# TIA_sep_amp_13_March.net
KiCad netlist of a schematic drawn in EAGLE
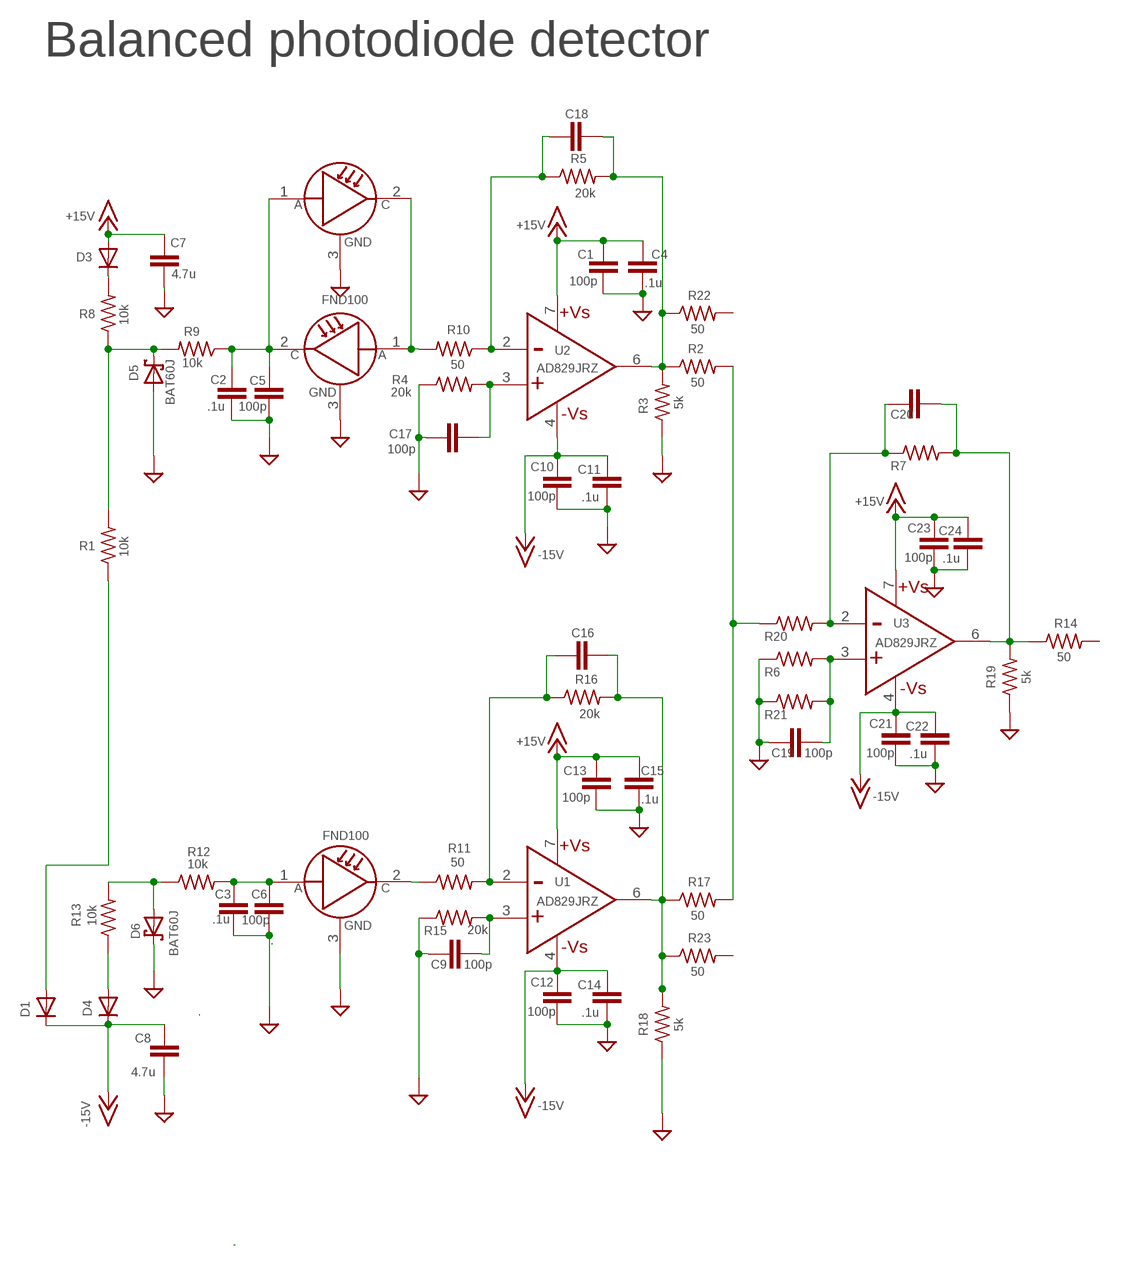
[diagram p0: schematic, sheet 1]

(export (version "E")
  (design (tool "Eeschema 10.0.6"))
  (components
    (comp (ref "C1")
      (value "100p")
      (footprint "eagle-import:C0603")
      (libsource (lib "eagle-import") (part "C-EUC0603"))
    )
    (comp (ref "C2")
      (value ".1u")
      (footprint "eagle-import:C0603")
      (libsource (lib "eagle-import") (part "C-EUC0603"))
    )
    (comp (ref "C3")
      (value ".1u")
      (footprint "eagle-import:C0603")
      (libsource (lib "eagle-import") (part "C-EUC0603"))
    )
    (comp (ref "C4")
      (value ".1u")
      (footprint "eagle-import:C0603")
      (libsource (lib "eagle-import") (part "C-EUC0603"))
    )
    (comp (ref "C5")
      (value "100p")
      (footprint "eagle-import:C0603")
      (libsource (lib "eagle-import") (part "C-EUC0603"))
    )
    (comp (ref "C6")
      (value "100p")
      (footprint "eagle-import:C0603")
      (libsource (lib "eagle-import") (part "C-EUC0603"))
    )
    (comp (ref "C7")
      (value "4.7u")
      (footprint "eagle-import:C5B2.5")
      (libsource (lib "eagle-import") (part "C5/2.5"))
    )
    (comp (ref "C8")
      (value "4.7u")
      (footprint "eagle-import:C5B2.5")
      (libsource (lib "eagle-import") (part "C5/2.5"))
    )
    (comp (ref "C9")
      (value "100p")
      (footprint "eagle-import:C0603")
      (libsource (lib "eagle-import") (part "C-EUC0603"))
    )
    (comp (ref "C10")
      (value "100p")
      (footprint "eagle-import:C0603")
      (libsource (lib "eagle-import") (part "C-EUC0603"))
    )
    (comp (ref "C11")
      (value ".1u")
      (footprint "eagle-import:C0603")
      (libsource (lib "eagle-import") (part "C-EUC0603"))
    )
    (comp (ref "C12")
      (value "100p")
      (footprint "eagle-import:C0603")
      (libsource (lib "eagle-import") (part "C-EUC0603"))
    )
    (comp (ref "C13")
      (value "100p")
      (footprint "eagle-import:C0603")
      (libsource (lib "eagle-import") (part "C-EUC0603"))
    )
    (comp (ref "C14")
      (value ".1u")
      (footprint "eagle-import:C0603")
      (libsource (lib "eagle-import") (part "C-EUC0603"))
    )
    (comp (ref "C15")
      (value ".1u")
      (footprint "eagle-import:C0603")
      (libsource (lib "eagle-import") (part "C-EUC0603"))
    )
    (comp (ref "C16")
      (value "C-EUC0603")
      (footprint "eagle-import:C0603")
      (libsource (lib "eagle-import") (part "C-EUC0603"))
    )
    (comp (ref "C17")
      (value "100p")
      (footprint "eagle-import:C0603")
      (libsource (lib "eagle-import") (part "C-EUC0603"))
    )
    (comp (ref "C18")
      (value "C-EUC0603")
      (footprint "eagle-import:C0603")
      (libsource (lib "eagle-import") (part "C-EUC0603"))
    )
    (comp (ref "C19")
      (value "100p")
      (footprint "eagle-import:C0603")
      (libsource (lib "eagle-import") (part "C-EUC0603"))
    )
    (comp (ref "C20")
      (value "100p")
      (footprint "eagle-import:C0603")
      (libsource (lib "eagle-import") (part "C-EUC0603"))
    )
    (comp (ref "C21")
      (value "100p")
      (footprint "eagle-import:C0603")
      (libsource (lib "eagle-import") (part "C-EUC0603"))
    )
    (comp (ref "C22")
      (value ".1u")
      (footprint "eagle-import:C0603")
      (libsource (lib "eagle-import") (part "C-EUC0603"))
    )
    (comp (ref "C23")
      (value "100p")
      (footprint "eagle-import:C0603")
      (libsource (lib "eagle-import") (part "C-EUC0603"))
    )
    (comp (ref "C24")
      (value ".1u")
      (footprint "eagle-import:C0603")
      (libsource (lib "eagle-import") (part "C-EUC0603"))
    )
    (comp (ref "D1")
      (value "SOD523DIODE")
      (footprint "eagle-import:SOD523")
      (libsource (lib "eagle-import") (part "SOD523DIODE"))
    )
    (comp (ref "D3")
      (value "SOD523DIODE")
      (footprint "eagle-import:SOD523")
      (libsource (lib "eagle-import") (part "SOD523DIODE"))
    )
    (comp (ref "D4")
      (value "SOD523DIODE")
      (footprint "eagle-import:SOD523")
      (libsource (lib "eagle-import") (part "SOD523DIODE"))
    )
    (comp (ref "D5")
      (value "BAT60J")
      (footprint "eagle-import:SOD323_ST")
      (libsource (lib "eagle-import") (part "BAT60J"))
    )
    (comp (ref "D6")
      (value "BAT60J")
      (footprint "eagle-import:SOD323_ST")
      (libsource (lib "eagle-import") (part "BAT60J"))
    )
    (comp (ref "R1")
      (value "10k")
      (footprint "eagle-import:R0603")
      (libsource (lib "eagle-import") (part "R-US_R0603"))
    )
    (comp (ref "R2")
      (value "50")
      (footprint "eagle-import:R0603")
      (libsource (lib "eagle-import") (part "R-US_R0603"))
    )
    (comp (ref "R3")
      (value "5k")
      (footprint "eagle-import:R0603")
      (libsource (lib "eagle-import") (part "R-US_R0603"))
    )
    (comp (ref "R4")
      (value "20k")
      (footprint "eagle-import:R0603")
      (libsource (lib "eagle-import") (part "R-US_R0603"))
    )
    (comp (ref "R5")
      (value "20k")
      (footprint "eagle-import:R0603")
      (libsource (lib "eagle-import") (part "R-US_R0603"))
    )
    (comp (ref "R6")
      (value "R-US_R0603")
      (footprint "eagle-import:R0603")
      (libsource (lib "eagle-import") (part "R-US_R0603"))
    )
    (comp (ref "R7")
      (value "R-US_R0603")
      (footprint "eagle-import:R0603")
      (libsource (lib "eagle-import") (part "R-US_R0603"))
    )
    (comp (ref "R8")
      (value "10k")
      (footprint "eagle-import:R0603")
      (libsource (lib "eagle-import") (part "R-US_R0603"))
    )
    (comp (ref "R9")
      (value "10k")
      (footprint "eagle-import:R0603")
      (libsource (lib "eagle-import") (part "R-US_R0603"))
    )
    (comp (ref "R10")
      (value "50")
      (footprint "eagle-import:R0603")
      (libsource (lib "eagle-import") (part "R-US_R0603"))
    )
    (comp (ref "R11")
      (value "50")
      (footprint "eagle-import:R0603")
      (libsource (lib "eagle-import") (part "R-US_R0603"))
    )
    (comp (ref "R12")
      (value "10k")
      (footprint "eagle-import:R0603")
      (libsource (lib "eagle-import") (part "R-US_R0603"))
    )
    (comp (ref "R13")
      (value "10k")
      (footprint "eagle-import:R0603")
      (libsource (lib "eagle-import") (part "R-US_R0603"))
    )
    (comp (ref "R14")
      (value "50")
      (footprint "eagle-import:R0603")
      (libsource (lib "eagle-import") (part "R-US_R0603"))
    )
    (comp (ref "R15")
      (value "20k")
      (footprint "eagle-import:R0603")
      (libsource (lib "eagle-import") (part "R-US_R0603"))
    )
    (comp (ref "R16")
      (value "20k")
      (footprint "eagle-import:R0603")
      (libsource (lib "eagle-import") (part "R-US_R0603"))
    )
    (comp (ref "R17")
      (value "50")
      (footprint "eagle-import:R0603")
      (libsource (lib "eagle-import") (part "R-US_R0603"))
    )
    (comp (ref "R18")
      (value "5k")
      (footprint "eagle-import:R0603")
      (libsource (lib "eagle-import") (part "R-US_R0603"))
    )
    (comp (ref "R19")
      (value "5k")
      (footprint "eagle-import:R0603")
      (libsource (lib "eagle-import") (part "R-US_R0603"))
    )
    (comp (ref "R20")
      (value "R-US_R0603")
      (footprint "eagle-import:R0603")
      (libsource (lib "eagle-import") (part "R-US_R0603"))
    )
    (comp (ref "R21")
      (value "R-US_R0603")
      (footprint "eagle-import:R0603")
      (libsource (lib "eagle-import") (part "R-US_R0603"))
    )
    (comp (ref "R22")
      (value "50")
      (footprint "eagle-import:R0603")
      (libsource (lib "eagle-import") (part "R-US_R0603"))
    )
    (comp (ref "R23")
      (value "50")
      (footprint "eagle-import:R0603")
      (libsource (lib "eagle-import") (part "R-US_R0603"))
    )
    (comp (ref "U$1")
      (value "FND100")
      (footprint "eagle-import:TO254P939X470-3P")
      (libsource (lib "eagle-import") (part "FND100"))
    )
    (comp (ref "U$2")
      (value "FND100")
      (footprint "eagle-import:TO254P939X470-3P")
      (libsource (lib "eagle-import") (part "FND100"))
    )
    (comp (ref "U$4")
      (value "FND100")
      (footprint "eagle-import:TO254P939X470-3P")
      (libsource (lib "eagle-import") (part "FND100"))
    )
    (comp (ref "U1")
      (value "AD829JRZ")
      (footprint "eagle-import:SOIC127P600X175-8N")
      (libsource (lib "eagle-import") (part "AD829JRZ"))
    )
    (comp (ref "U2")
      (value "AD829JRZ")
      (footprint "eagle-import:SOIC127P600X175-8N")
      (libsource (lib "eagle-import") (part "AD829JRZ"))
    )
    (comp (ref "U3")
      (value "AD829JRZ")
      (footprint "eagle-import:SOIC127P600X175-8N")
      (libsource (lib "eagle-import") (part "AD829JRZ"))
    )
  )
  (nets
    (net (code "1") (name "+15V") (class "Default")
      (node (ref "C1") (pin "2") (pinfunction "2_2") (pintype "passive"))
      (node (ref "C13") (pin "2") (pinfunction "2_2") (pintype "passive"))
      (node (ref "C15") (pin "2") (pinfunction "2_2") (pintype "passive"))
      (node (ref "C23") (pin "2") (pinfunction "2_2") (pintype "passive"))
      (node (ref "C24") (pin "2") (pinfunction "2_2") (pintype "passive"))
      (node (ref "C4") (pin "2") (pinfunction "2_2") (pintype "passive"))
      (node (ref "C7") (pin "1") (pinfunction "1_1") (pintype "passive"))
      (node (ref "D3") (pin "A") (pinfunction "A_A") (pintype "passive"))
      (node (ref "U1") (pin "7") (pinfunction "+VS_7") (pintype "power_in"))
      (node (ref "U2") (pin "7") (pinfunction "+VS_7") (pintype "power_in"))
      (node (ref "U3") (pin "7") (pinfunction "+VS_7") (pintype "power_in"))
    )
    (net (code "2") (name "-15V") (class "Default")
      (node (ref "C10") (pin "2") (pinfunction "2_2") (pintype "passive"))
      (node (ref "C11") (pin "2") (pinfunction "2_2") (pintype "passive"))
      (node (ref "C12") (pin "2") (pinfunction "2_2") (pintype "passive"))
      (node (ref "C14") (pin "2") (pinfunction "2_2") (pintype "passive"))
      (node (ref "C21") (pin "2") (pinfunction "2_2") (pintype "passive"))
      (node (ref "C22") (pin "2") (pinfunction "2_2") (pintype "passive"))
      (node (ref "C8") (pin "2") (pinfunction "2_2") (pintype "passive"))
      (node (ref "D1") (pin "C") (pinfunction "C_C") (pintype "passive"))
      (node (ref "D4") (pin "C") (pinfunction "C_C") (pintype "passive"))
      (node (ref "U1") (pin "4") (pinfunction "-VS_4") (pintype "power_in"))
      (node (ref "U2") (pin "4") (pinfunction "-VS_4") (pintype "power_in"))
      (node (ref "U3") (pin "4") (pinfunction "-VS_4") (pintype "power_in"))
    )
    (net (code "3") (name "GND") (class "Default")
      (node (ref "C1") (pin "1") (pinfunction "1_1") (pintype "passive"))
      (node (ref "C10") (pin "1") (pinfunction "1_1") (pintype "passive"))
      (node (ref "C11") (pin "1") (pinfunction "1_1") (pintype "passive"))
      (node (ref "C12") (pin "1") (pinfunction "1_1") (pintype "passive"))
      (node (ref "C13") (pin "1") (pinfunction "1_1") (pintype "passive"))
      (node (ref "C14") (pin "1") (pinfunction "1_1") (pintype "passive"))
      (node (ref "C15") (pin "1") (pinfunction "1_1") (pintype "passive"))
      (node (ref "C17") (pin "1") (pinfunction "1_1") (pintype "passive"))
      (node (ref "C19") (pin "1") (pinfunction "1_1") (pintype "passive"))
      (node (ref "C2") (pin "1") (pinfunction "1_1") (pintype "passive"))
      (node (ref "C21") (pin "1") (pinfunction "1_1") (pintype "passive"))
      (node (ref "C22") (pin "1") (pinfunction "1_1") (pintype "passive"))
      (node (ref "C23") (pin "1") (pinfunction "1_1") (pintype "passive"))
      (node (ref "C24") (pin "1") (pinfunction "1_1") (pintype "passive"))
      (node (ref "C3") (pin "1") (pinfunction "1_1") (pintype "passive"))
      (node (ref "C4") (pin "1") (pinfunction "1_1") (pintype "passive"))
      (node (ref "C5") (pin "1") (pinfunction "1_1") (pintype "passive"))
      (node (ref "C6") (pin "1") (pinfunction "1_1") (pintype "passive"))
      (node (ref "C7") (pin "2") (pinfunction "2_2") (pintype "passive"))
      (node (ref "C8") (pin "1") (pinfunction "1_1") (pintype "passive"))
      (node (ref "C9") (pin "1") (pinfunction "1_1") (pintype "passive"))
      (node (ref "D5") (pin "A") (pinfunction "A_A") (pintype "passive"))
      (node (ref "D6") (pin "C") (pinfunction "C_C") (pintype "passive"))
      (node (ref "R15") (pin "1") (pinfunction "1_1") (pintype "passive"))
      (node (ref "R18") (pin "1") (pinfunction "1_1") (pintype "passive"))
      (node (ref "R19") (pin "1") (pinfunction "1_1") (pintype "passive"))
      (node (ref "R21") (pin "1") (pinfunction "1_1") (pintype "passive"))
      (node (ref "R3") (pin "1") (pinfunction "1_1") (pintype "passive"))
      (node (ref "R4") (pin "1") (pinfunction "1_1") (pintype "passive"))
      (node (ref "R6") (pin "1") (pinfunction "1_1") (pintype "passive"))
      (node (ref "U$1") (pin "3") (pinfunction "GND_3") (pintype "bidirectional"))
      (node (ref "U$2") (pin "3") (pinfunction "GND_3") (pintype "bidirectional"))
      (node (ref "U$4") (pin "3") (pinfunction "GND_3") (pintype "bidirectional"))
    )
    (net (code "4") (name "Net-(D1-PadA)") (class "Default")
      (node (ref "D1") (pin "A") (pinfunction "A_A") (pintype "passive"))
      (node (ref "R1") (pin "1") (pinfunction "1_1") (pintype "passive"))
    )
    (net (code "5") (name "Net-(D3-PadC)") (class "Default")
      (node (ref "D3") (pin "C") (pinfunction "C_C") (pintype "passive"))
      (node (ref "R8") (pin "2") (pinfunction "2_2") (pintype "passive"))
    )
    (net (code "6") (name "Net-(D4-PadA)") (class "Default")
      (node (ref "D4") (pin "A") (pinfunction "A_A") (pintype "passive"))
      (node (ref "R13") (pin "1") (pinfunction "1_1") (pintype "passive"))
    )
    (net (code "7") (name "Net-(D5-PadC)") (class "Default")
      (node (ref "D5") (pin "C") (pinfunction "C_C") (pintype "passive"))
      (node (ref "R1") (pin "2") (pinfunction "2_2") (pintype "passive"))
      (node (ref "R8") (pin "1") (pinfunction "1_1") (pintype "passive"))
      (node (ref "R9") (pin "2") (pinfunction "2_2") (pintype "passive"))
    )
    (net (code "8") (name "Net-(D6-PadA)") (class "Default")
      (node (ref "D6") (pin "A") (pinfunction "A_A") (pintype "passive"))
      (node (ref "R12") (pin "1") (pinfunction "1_1") (pintype "passive"))
      (node (ref "R13") (pin "2") (pinfunction "2_2") (pintype "passive"))
    )
    (net (code "9") (name "Net-(R17-Pad2)") (class "Default")
      (node (ref "R17") (pin "2") (pinfunction "2_2") (pintype "passive"))
      (node (ref "R2") (pin "2") (pinfunction "2_2") (pintype "passive"))
      (node (ref "R20") (pin "1") (pinfunction "1_1") (pintype "passive"))
    )
    (net (code "10") (name "Net-(U$1-A)") (class "Default")
      (node (ref "R10") (pin "2") (pinfunction "2_2") (pintype "passive"))
      (node (ref "U$1") (pin "1") (pinfunction "A_1") (pintype "bidirectional"))
      (node (ref "U$4") (pin "2") (pinfunction "C_2") (pintype "bidirectional"))
    )
    (net (code "11") (name "Net-(U$1-C)") (class "Default")
      (node (ref "C2") (pin "2") (pinfunction "2_2") (pintype "passive"))
      (node (ref "C5") (pin "2") (pinfunction "2_2") (pintype "passive"))
      (node (ref "R9") (pin "1") (pinfunction "1_1") (pintype "passive"))
      (node (ref "U$1") (pin "2") (pinfunction "C_2") (pintype "bidirectional"))
      (node (ref "U$4") (pin "1") (pinfunction "A_1") (pintype "bidirectional"))
    )
    (net (code "12") (name "Net-(U$2-A)") (class "Default")
      (node (ref "C3") (pin "2") (pinfunction "2_2") (pintype "passive"))
      (node (ref "C6") (pin "2") (pinfunction "2_2") (pintype "passive"))
      (node (ref "R12") (pin "2") (pinfunction "2_2") (pintype "passive"))
      (node (ref "U$2") (pin "1") (pinfunction "A_1") (pintype "bidirectional"))
    )
    (net (code "13") (name "Net-(U$2-C)") (class "Default")
      (node (ref "R11") (pin "1") (pinfunction "1_1") (pintype "passive"))
      (node (ref "U$2") (pin "2") (pinfunction "C_2") (pintype "bidirectional"))
    )
    (net (code "14") (name "Net-(U1-+IN)") (class "Default")
      (node (ref "C9") (pin "2") (pinfunction "2_2") (pintype "passive"))
      (node (ref "R15") (pin "2") (pinfunction "2_2") (pintype "passive"))
      (node (ref "U1") (pin "3") (pinfunction "+IN_3") (pintype "input"))
    )
    (net (code "15") (name "Net-(U1--IN)") (class "Default")
      (node (ref "C16") (pin "1") (pinfunction "1_1") (pintype "passive"))
      (node (ref "R11") (pin "2") (pinfunction "2_2") (pintype "passive"))
      (node (ref "R16") (pin "1") (pinfunction "1_1") (pintype "passive"))
      (node (ref "U1") (pin "2") (pinfunction "-IN_2") (pintype "input"))
    )
    (net (code "16") (name "Net-(U1-OUTPUT)") (class "Default")
      (node (ref "C16") (pin "2") (pinfunction "2_2") (pintype "passive"))
      (node (ref "R16") (pin "2") (pinfunction "2_2") (pintype "passive"))
      (node (ref "R17") (pin "1") (pinfunction "1_1") (pintype "passive"))
      (node (ref "R18") (pin "2") (pinfunction "2_2") (pintype "passive"))
      (node (ref "R23") (pin "1") (pinfunction "1_1") (pintype "passive"))
      (node (ref "U1") (pin "6") (pinfunction "OUTPUT_6") (pintype "output"))
    )
    (net (code "17") (name "Net-(U2-+IN)") (class "Default")
      (node (ref "C17") (pin "2") (pinfunction "2_2") (pintype "passive"))
      (node (ref "R4") (pin "2") (pinfunction "2_2") (pintype "passive"))
      (node (ref "U2") (pin "3") (pinfunction "+IN_3") (pintype "input"))
    )
    (net (code "18") (name "Net-(U2--IN)") (class "Default")
      (node (ref "C18") (pin "1") (pinfunction "1_1") (pintype "passive"))
      (node (ref "R10") (pin "1") (pinfunction "1_1") (pintype "passive"))
      (node (ref "R5") (pin "1") (pinfunction "1_1") (pintype "passive"))
      (node (ref "U2") (pin "2") (pinfunction "-IN_2") (pintype "input"))
    )
    (net (code "19") (name "Net-(U2-OUTPUT)") (class "Default")
      (node (ref "C18") (pin "2") (pinfunction "2_2") (pintype "passive"))
      (node (ref "R2") (pin "1") (pinfunction "1_1") (pintype "passive"))
      (node (ref "R22") (pin "1") (pinfunction "1_1") (pintype "passive"))
      (node (ref "R3") (pin "2") (pinfunction "2_2") (pintype "passive"))
      (node (ref "R5") (pin "2") (pinfunction "2_2") (pintype "passive"))
      (node (ref "U2") (pin "6") (pinfunction "OUTPUT_6") (pintype "output"))
    )
    (net (code "20") (name "Net-(U3-+IN)") (class "Default")
      (node (ref "C19") (pin "2") (pinfunction "2_2") (pintype "passive"))
      (node (ref "R21") (pin "2") (pinfunction "2_2") (pintype "passive"))
      (node (ref "R6") (pin "2") (pinfunction "2_2") (pintype "passive"))
      (node (ref "U3") (pin "3") (pinfunction "+IN_3") (pintype "input"))
    )
    (net (code "21") (name "Net-(U3--IN)") (class "Default")
      (node (ref "C20") (pin "1") (pinfunction "1_1") (pintype "passive"))
      (node (ref "R20") (pin "2") (pinfunction "2_2") (pintype "passive"))
      (node (ref "R7") (pin "1") (pinfunction "1_1") (pintype "passive"))
      (node (ref "U3") (pin "2") (pinfunction "-IN_2") (pintype "input"))
    )
    (net (code "22") (name "Net-(U3-OUTPUT)") (class "Default")
      (node (ref "C20") (pin "2") (pinfunction "2_2") (pintype "passive"))
      (node (ref "R14") (pin "1") (pinfunction "1_1") (pintype "passive"))
      (node (ref "R19") (pin "2") (pinfunction "2_2") (pintype "passive"))
      (node (ref "R7") (pin "2") (pinfunction "2_2") (pintype "passive"))
      (node (ref "U3") (pin "6") (pinfunction "OUTPUT_6") (pintype "output"))
    )
    (net (code "23") (name "unconnected-(R14-Pad2)") (class "Default")
      (node (ref "R14") (pin "2") (pinfunction "2_2") (pintype "passive"))
    )
    (net (code "24") (name "unconnected-(R22-Pad2)") (class "Default")
      (node (ref "R22") (pin "2") (pinfunction "2_2") (pintype "passive"))
    )
    (net (code "25") (name "unconnected-(R23-Pad2)") (class "Default")
      (node (ref "R23") (pin "2") (pinfunction "2_2") (pintype "passive"))
    )
  )
)
